# Cell.net
KiCad netlist of a schematic drawn in Altium Designer
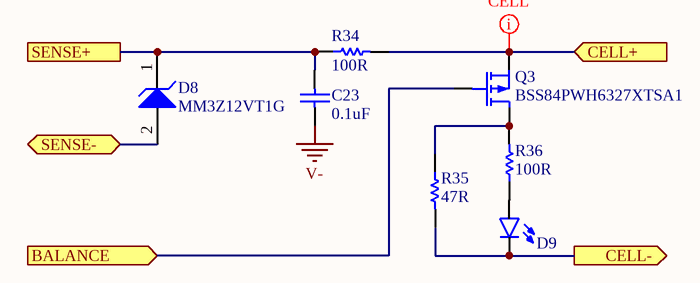
[diagram p0: Cell.SchDoc]

(export (version "E")
  (design (tool "Eeschema 10.0.6"))
  (components
    (comp (ref "C23")
      (value "0.1uF")
      (footprint "C0603[1608X92]")
      (description "0.1uF 100V 10% 0603 (1608 Metric)")
      (fields (field (name "PARTNUMBER") "GRM188R72A104KA35D") (field (name "MANUFACTURER") "Murata"))
      (libsource (lib "Capacitors") (part "CAP_0.1uF_100V_0603_10%"))
    )
    (comp (ref "D8")
      (value "MM3Z12VT1G")
      (footprint "SOD-323")
      (description "Zener Voltage Regulator, 300 mW, 2-Pin SOD-323, Tape and Reel")
      (fields (field (name "MANUFACTURER") "ON Semiconductor"))
      (libsource (lib "Diodes") (part "MM3Z12VT1G"))
    )
    (comp (ref "D9")
      (value "LED_0603_BLUE_5mA")
      (footprint "LED0603")
      (fields (field (name "PARTNUMBER") "LTST-C193TBKT-5A") (field (name "MANUFACTURER") "Lite-On Inc."))
      (libsource (lib "LEDs") (part "LED_0603_BLUE_5mA"))
    )
    (comp (ref "Q3")
      (value "BSS84PWH6327XTSA1")
      (footprint "SOT323-3")
      (description "P-Channel MOSFET")
      (fields (field (name "MANUFACTURER") "Infineon"))
      (libsource (lib "MOSFETs") (part "BSS84PW H6327"))
    )
    (comp (ref "R34")
      (value "100R")
      (footprint "R0603[1608]")
      (description "100R 0.25W 1% 0603 (1005 Metric)")
      (fields (field (name "MANUFACTURER") "Vishay / Dale") (field (name "PARTNUMBER") "CRCW0603100RFKEAHP"))
      (libsource (lib "Resistors") (part "RES_100R_0603_1%"))
    )
    (comp (ref "R35")
      (value "47R")
      (footprint "R0805[2012]")
      (description "47R 0.5W 5% 0805 (2012 Metric)")
      (fields (field (name "TOLERANCE") "5%") (field (name "POWER") "0.5W"))
      (libsource (lib "Resistors") (part "RES_47R_0805_5%"))
    )
    (comp (ref "R36")
      (value "100R")
      (footprint "R0603[1608]")
      (description "100R 0.25W 1% 0603 (1005 Metric)")
      (fields (field (name "MANUFACTURER") "Vishay / Dale") (field (name "PARTNUMBER") "CRCW0603100RFKEAHP"))
      (libsource (lib "Resistors") (part "RES_100R_0603_1%"))
    )
  )
  (nets
    (net (code "1") (name "/BALANCE") (class "Default")
      (node (ref "Q3") (pin "1") (pinfunction "G_1") (pintype "passive"))
    )
    (net (code "2") (name "/CELL+") (class "Default")
      (node (ref "Q3") (pin "2") (pinfunction "S_2") (pintype "passive"))
      (node (ref "R34") (pin "1") (pinfunction "1_1") (pintype "passive"))
    )
    (net (code "3") (name "/CELL-") (class "Default")
      (node (ref "D9") (pin "C") (pinfunction "C_C") (pintype "passive"))
      (node (ref "R35") (pin "1") (pinfunction "1_1") (pintype "passive"))
    )
    (net (code "4") (name "/SENSE+") (class "Default")
      (node (ref "C23") (pin "2") (pinfunction "2_2") (pintype "passive"))
      (node (ref "D8") (pin "1") (pinfunction "K_1") (pintype "passive"))
      (node (ref "R34") (pin "2") (pinfunction "2_2") (pintype "passive"))
    )
    (net (code "5") (name "/SENSE-") (class "Default")
      (node (ref "D8") (pin "2") (pinfunction "A_2") (pintype "passive"))
    )
    (net (code "6") (name "Net-(D9-PadA)") (class "Default")
      (node (ref "D9") (pin "A") (pinfunction "A_A") (pintype "passive"))
      (node (ref "R36") (pin "2") (pinfunction "2_2") (pintype "passive"))
    )
    (net (code "7") (name "Net-(Q3-D)") (class "Default")
      (node (ref "Q3") (pin "3") (pinfunction "D_3") (pintype "passive"))
      (node (ref "R35") (pin "2") (pinfunction "2_2") (pintype "passive"))
      (node (ref "R36") (pin "1") (pinfunction "1_1") (pintype "passive"))
    )
    (net (code "8") (name "V-") (class "Default")
      (node (ref "C23") (pin "1") (pinfunction "1_1") (pintype "passive"))
    )
  )
)
